# PWR_CTRL.net
KiCad netlist of a schematic drawn in Altium Designer
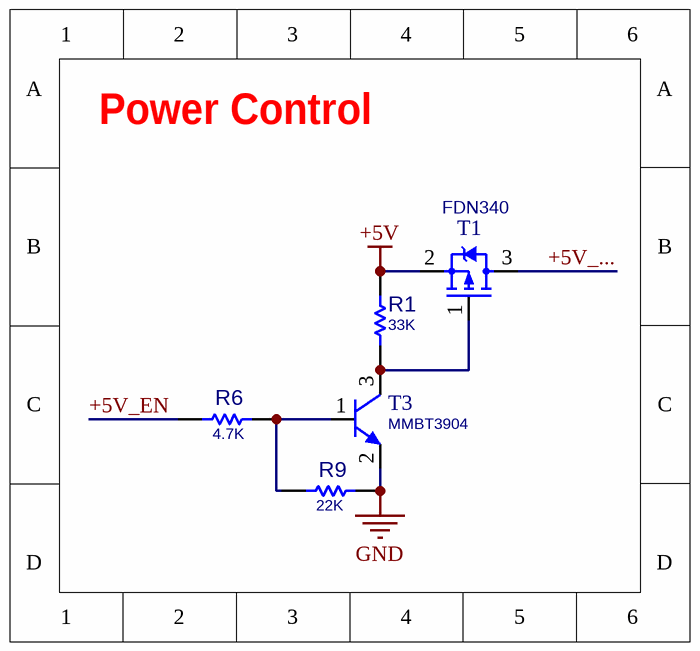
[diagram p0: PWR CTRL.SchDoc]

(export (version "E")
  (design (tool "Eeschema 10.0.6"))
  (components
    (comp (ref "R1")
      (value "33K")
      (footprint "R0603")
      (description "RES, SMD")
      (fields (field (name "MANF_P#") "RK73H1ETTP4701F") (field (name "MANF") "KOA SPEER"))
      (libsource (lib "PW Components 97_481") (part "RES_SMD"))
    )
    (comp (ref "R6")
      (value "4.7K")
      (footprint "R0603")
      (description "RES, SMD")
      (fields (field (name "MANF_P#") "RK73H1ETTP4701F") (field (name "MANF") "KOA SPEER"))
      (libsource (lib "PW Components 97_481") (part "RES_SMD"))
    )
    (comp (ref "R9")
      (value "22K")
      (footprint "R0603")
      (description "RES, SMD")
      (fields (field (name "MANF_P#") "RK73H1ETTP4701F") (field (name "MANF") "KOA SPEER"))
      (libsource (lib "PW Components 97_481") (part "RES_SMD"))
    )
    (comp (ref "T1")
      (value "FDN340")
      (footprint "SOT23_3")
      (description "MOSFET SMD P-CH 20V 2A")
      (fields (field (name "MANF_P#") "FDN360"))
      (libsource (lib "Transistor FET") (part "MOSP_FDN340_SOT23"))
    )
    (comp (ref "T3")
      (value "MMBT3904")
      (footprint "SOT23_3")
      (description "BJT, NPN, 40v, 0.2A, SMD, SOT23")
      (fields (field (name "MANF") "Diodes, NXP, FAIRCHILD, ON"))
      (libsource (lib "Transistor BJT") (part "NPN_MMBT3904_SOT23"))
    )
  )
  (nets
    (net (code "1") (name "+5V") (class "Default")
      (node (ref "R1") (pin "2") (pinfunction "2_2") (pintype "passive"))
      (node (ref "T1") (pin "2") (pinfunction "S_2") (pintype "passive"))
    )
    (net (code "2") (name "/+5V_...") (class "Default")
      (node (ref "T1") (pin "3") (pinfunction "D_3") (pintype "passive"))
    )
    (net (code "3") (name "/+5V_EN") (class "Default")
      (node (ref "R6") (pin "2") (pinfunction "2_2") (pintype "passive"))
    )
    (net (code "4") (name "GND") (class "Default")
      (node (ref "R9") (pin "1") (pinfunction "1_1") (pintype "passive"))
      (node (ref "T3") (pin "2") (pinfunction "E_2") (pintype "passive"))
    )
    (net (code "5") (name "Net-(T3-B)") (class "Default")
      (node (ref "R6") (pin "1") (pinfunction "1_1") (pintype "passive"))
      (node (ref "R9") (pin "2") (pinfunction "2_2") (pintype "passive"))
      (node (ref "T3") (pin "1") (pinfunction "B_1") (pintype "passive"))
    )
    (net (code "6") (name "Net-(T3-C)") (class "Default")
      (node (ref "R1") (pin "1") (pinfunction "1_1") (pintype "passive"))
      (node (ref "T1") (pin "1") (pinfunction "D_1") (pintype "passive"))
      (node (ref "T3") (pin "3") (pinfunction "C_3") (pintype "passive"))
    )
  )
)
